# USB.net
KiCad netlist of a schematic drawn in Altium Designer
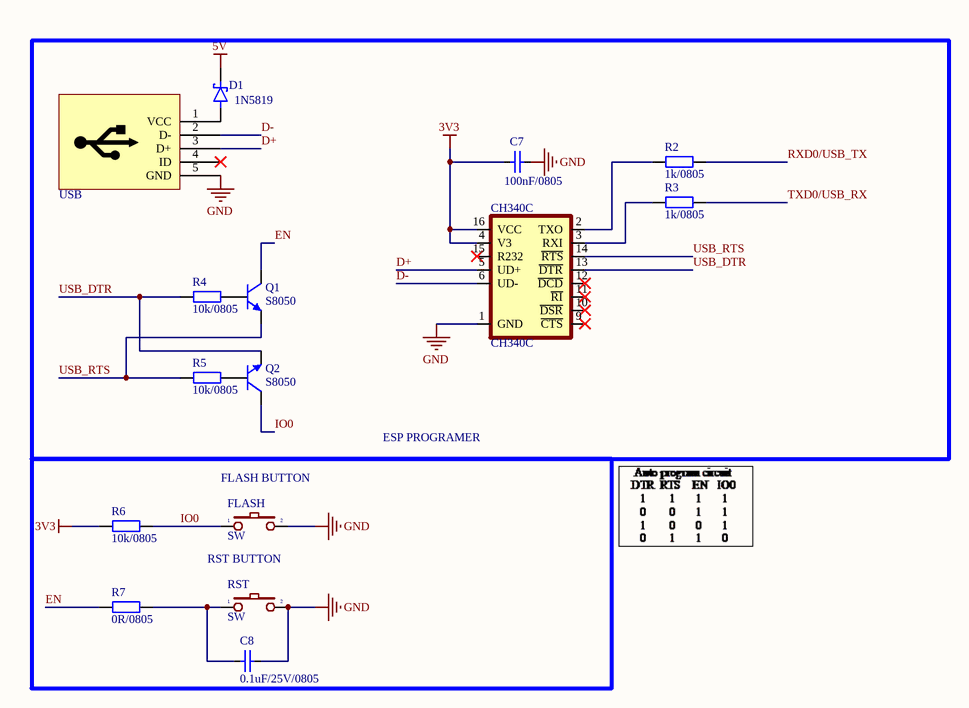
[diagram p0: USB.SchDoc]

(export (version "E")
  (design (tool "Eeschema 10.0.6"))
  (components
    (comp (ref "C7")
      (value "100nF/0805")
      (footprint "CAP_0805")
      (description "Capacitor")
      (fields (field (name "PUBLISHER") "Altium Limited"))
      (libsource (lib "My Library") (part "CapSMD"))
    )
    (comp (ref "C8")
      (value "0.1uF/25V/0805")
      (footprint "CAP_0805")
      (description "Capacitor")
      (fields (field (name "PUBLISHER") "Altium Limited"))
      (libsource (lib "My Library") (part "CapSMD"))
    )
    (comp (ref "CH340C")
      (value "CH340C")
      (footprint "SOP-16")
      (description "USB to serial chip CH340")
      (fields (field (name "MF") "WCH"))
      (libsource (lib "My Library") (part "CH340C"))
    )
    (comp (ref "D1")
      (value "1N5819")
      (footprint "SOD3715X145N")
      (description "Diode Schottky 40 V 1A Surface Mount SOD-123")
      (fields (field (name "MF") "Diodes Inc.") (field (name "MP") "1N5819HW-7-F"))
      (libsource (lib "1N5819HW-7-F") (part "1N5819HW-7-F"))
    )
    (comp (ref "FLASH")
      (value "SW")
      (footprint "SW-SMD")
      (description "Switch button 2 pin")
      (libsource (lib "My Library") (part "SW2"))
    )
    (comp (ref "Q1")
      (value "S8050")
      (footprint "SOT23")
      (description "NPN General")
      (fields (field (name "PUBLISHER") "Altium Limited"))
      (libsource (lib "My Library") (part "NPN"))
    )
    (comp (ref "Q2")
      (value "S8050")
      (footprint "SOT23")
      (description "NPN General")
      (fields (field (name "PUBLISHER") "Altium Limited"))
      (libsource (lib "My Library") (part "NPN"))
    )
    (comp (ref "R2")
      (value "1k/0805")
      (footprint "RES-SMD-0805")
      (description "Resistor SMD")
      (fields
        (field (name "MANUFACTURER") "Generic Components")
        (field (name "PUBLISHER") "Altium Hobart Technology Centre")
      )
      (libsource (lib "My Library") (part "Resistor - SMD"))
    )
    (comp (ref "R3")
      (value "1k/0805")
      (footprint "RES-SMD-0805")
      (description "Resistor SMD")
      (fields
        (field (name "MANUFACTURER") "Generic Components")
        (field (name "PUBLISHER") "Altium Hobart Technology Centre")
      )
      (libsource (lib "My Library") (part "Resistor - SMD"))
    )
    (comp (ref "R4")
      (value "10k/0805")
      (footprint "RES-SMD-0805")
      (description "Resistor SMD")
      (fields
        (field (name "MANUFACTURER") "Generic Components")
        (field (name "PUBLISHER") "Altium Hobart Technology Centre")
      )
      (libsource (lib "My Library") (part "Resistor - SMD"))
    )
    (comp (ref "R5")
      (value "10k/0805")
      (footprint "RES-SMD-0805")
      (description "Resistor SMD")
      (fields
        (field (name "MANUFACTURER") "Generic Components")
        (field (name "PUBLISHER") "Altium Hobart Technology Centre")
      )
      (libsource (lib "My Library") (part "Resistor - SMD"))
    )
    (comp (ref "R6")
      (value "10k/0805")
      (footprint "RES-SMD-0805")
      (description "Resistor SMD")
      (fields
        (field (name "MANUFACTURER") "Generic Components")
        (field (name "PUBLISHER") "Altium Hobart Technology Centre")
      )
      (libsource (lib "My Library") (part "Resistor - SMD"))
    )
    (comp (ref "R7")
      (value "0R/0805")
      (footprint "RES-SMD-0805")
      (description "Resistor SMD")
      (fields
        (field (name "MANUFACTURER") "Generic Components")
        (field (name "PUBLISHER") "Altium Hobart Technology Centre")
      )
      (libsource (lib "My Library") (part "Resistor - SMD"))
    )
    (comp (ref "RST")
      (value "SW")
      (footprint "SW-SMD")
      (description "Switch button 2 pin")
      (libsource (lib "My Library") (part "SW2"))
    )
    (comp (ref "USB")
      (value "USB")
      (footprint "HRS_ZX62D-B-5P8")
      (libsource (lib "My Library") (part "USB-M"))
    )
  )
  (nets
    (net (code "1") (name "/D+") (class "Default")
      (node (ref "CH340C") (pin "5") (pinfunction "UD+_5") (pintype "bidirectional"))
      (node (ref "USB") (pin "3") (pinfunction "D+_3") (pintype "passive"))
    )
    (net (code "2") (name "/D-") (class "Default")
      (node (ref "CH340C") (pin "6") (pinfunction "UD-_6") (pintype "bidirectional"))
      (node (ref "USB") (pin "2") (pinfunction "D-_2") (pintype "passive"))
    )
    (net (code "3") (name "/EN") (class "Default")
      (node (ref "Q1") (pin "2") (pinfunction "C_2") (pintype "passive"))
      (node (ref "R7") (pin "2") (pinfunction "2_2") (pintype "passive"))
    )
    (net (code "4") (name "/IO0") (class "Default")
      (node (ref "FLASH") (pin "1") (pinfunction "1_1") (pintype "passive"))
      (node (ref "Q2") (pin "2") (pinfunction "C_2") (pintype "passive"))
      (node (ref "R6") (pin "1") (pinfunction "1_1") (pintype "passive"))
    )
    (net (code "5") (name "/RXD0{slash}USB_TX") (class "Default")
      (node (ref "R2") (pin "2") (pinfunction "2_2") (pintype "passive"))
    )
    (net (code "6") (name "/TXD0{slash}USB_RX") (class "Default")
      (node (ref "R3") (pin "2") (pinfunction "2_2") (pintype "passive"))
    )
    (net (code "7") (name "/USB_DTR") (class "Default")
      (node (ref "CH340C") (pin "13") (pinfunction "~{DTR}_13") (pintype "bidirectional"))
      (node (ref "Q2") (pin "1") (pinfunction "E_1") (pintype "passive"))
      (node (ref "R4") (pin "2") (pinfunction "2_2") (pintype "passive"))
    )
    (net (code "8") (name "/USB_RTS") (class "Default")
      (node (ref "CH340C") (pin "14") (pinfunction "~{RTS}_14") (pintype "bidirectional"))
      (node (ref "Q1") (pin "1") (pinfunction "E_1") (pintype "passive"))
      (node (ref "R5") (pin "2") (pinfunction "2_2") (pintype "passive"))
    )
    (net (code "9") (name "3V3") (class "Default")
      (node (ref "C7") (pin "1") (pinfunction "1_1") (pintype "passive"))
      (node (ref "CH340C") (pin "16") (pinfunction "VCC_16") (pintype "bidirectional"))
      (node (ref "CH340C") (pin "4") (pinfunction "V3_4") (pintype "bidirectional"))
      (node (ref "R6") (pin "2") (pinfunction "2_2") (pintype "passive"))
    )
    (net (code "10") (name "5V") (class "Default")
      (node (ref "D1") (pin "C") (pinfunction "K_C") (pintype "passive"))
    )
    (net (code "11") (name "GND") (class "Default")
      (node (ref "C7") (pin "2") (pinfunction "2_2") (pintype "passive"))
      (node (ref "C8") (pin "2") (pinfunction "2_2") (pintype "passive"))
      (node (ref "CH340C") (pin "1") (pinfunction "GND_1") (pintype "bidirectional"))
      (node (ref "FLASH") (pin "2") (pinfunction "2_2") (pintype "passive"))
      (node (ref "RST") (pin "2") (pinfunction "2_2") (pintype "passive"))
      (node (ref "USB") (pin "5") (pinfunction "GND_5") (pintype "passive"))
    )
    (net (code "12") (name "Net-(C8-Pad1)") (class "Default")
      (node (ref "C8") (pin "1") (pinfunction "1_1") (pintype "passive"))
      (node (ref "R7") (pin "1") (pinfunction "1_1") (pintype "passive"))
      (node (ref "RST") (pin "1") (pinfunction "1_1") (pintype "passive"))
    )
    (net (code "13") (name "Net-(CH340C-RXI)") (class "Default")
      (node (ref "CH340C") (pin "3") (pinfunction "RXI_3") (pintype "bidirectional"))
      (node (ref "R3") (pin "1") (pinfunction "1_1") (pintype "passive"))
    )
    (net (code "14") (name "Net-(CH340C-TXO)") (class "Default")
      (node (ref "CH340C") (pin "2") (pinfunction "TXO_2") (pintype "bidirectional"))
      (node (ref "R2") (pin "1") (pinfunction "1_1") (pintype "passive"))
    )
    (net (code "15") (name "Net-(Q1-B)") (class "Default")
      (node (ref "Q1") (pin "3") (pinfunction "B_3") (pintype "passive"))
      (node (ref "R4") (pin "1") (pinfunction "1_1") (pintype "passive"))
    )
    (net (code "16") (name "Net-(Q2-B)") (class "Default")
      (node (ref "Q2") (pin "3") (pinfunction "B_3") (pintype "passive"))
      (node (ref "R5") (pin "1") (pinfunction "1_1") (pintype "passive"))
    )
    (net (code "17") (name "Net-(USB-VCC)") (class "Default")
      (node (ref "D1") (pin "A") (pinfunction "A_A") (pintype "passive"))
      (node (ref "USB") (pin "1") (pinfunction "VCC_1") (pintype "passive"))
    )
    (net (code "18") (name "unconnected-(CH340C-R232-Pad15)") (class "Default")
      (node (ref "CH340C") (pin "15") (pinfunction "R232_15") (pintype "bidirectional+no_connect"))
    )
    (net (code "19") (name "unconnected-(CH340C-~{CTS}-Pad9)") (class "Default")
      (node (ref "CH340C") (pin "9") (pinfunction "~{CTS}_9") (pintype "bidirectional+no_connect"))
    )
    (net (code "20") (name "unconnected-(CH340C-~{DCD}-Pad12)") (class "Default")
      (node (ref "CH340C") (pin "12") (pinfunction "~{DCD}_12") (pintype "bidirectional+no_connect"))
    )
    (net (code "21") (name "unconnected-(CH340C-~{DSR}-Pad10)") (class "Default")
      (node (ref "CH340C") (pin "10") (pinfunction "~{DSR}_10") (pintype "bidirectional+no_connect"))
    )
    (net (code "22") (name "unconnected-(CH340C-~{RI}-Pad11)") (class "Default")
      (node (ref "CH340C") (pin "11") (pinfunction "~{RI}_11") (pintype "bidirectional+no_connect"))
    )
    (net (code "23") (name "unconnected-(USB-ID-Pad4)") (class "Default")
      (node (ref "USB") (pin "4") (pinfunction "ID_4") (pintype "passive+no_connect"))
    )
  )
)
